# KNOBS.net
KiCad netlist of a schematic drawn in Altium Designer
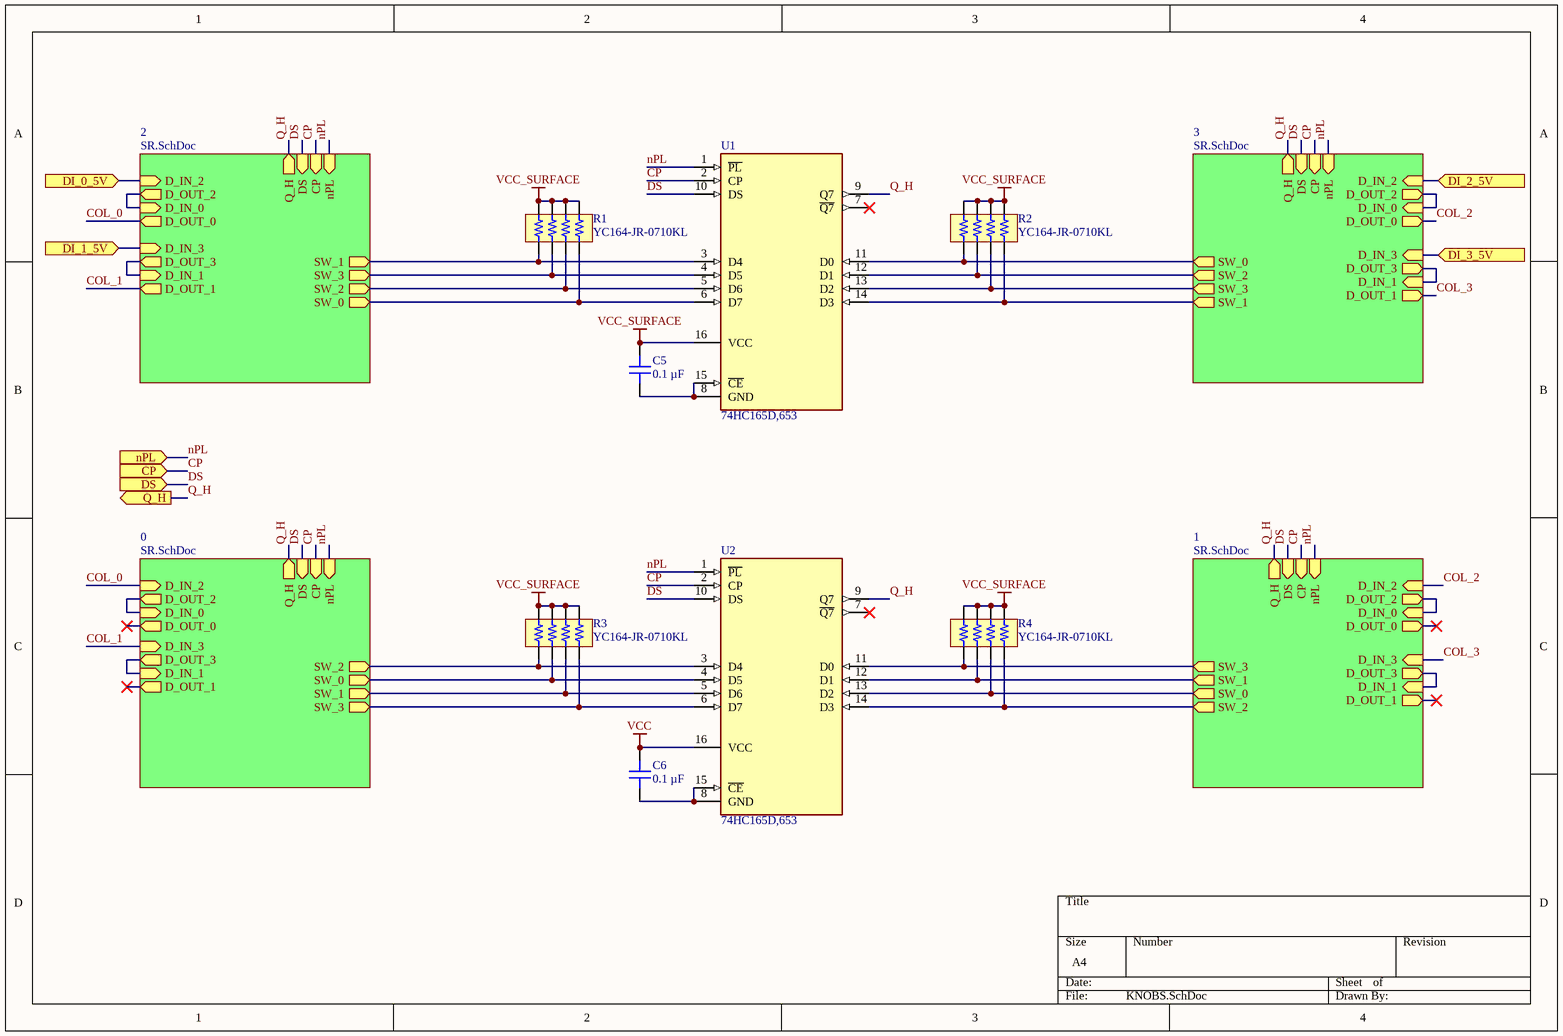
[diagram p0: KNOBS.SchDoc]

(export (version "E")
  (design (tool "Eeschema 10.0.6"))
  (components
    (comp (ref "C5")
      (value "0.1 µF")
      (footprint "CAP 0603_1608")
      (description "CAP CER 0.1UF 16V X7R 0603")
      (fields (field (name "PART NUMBER") "CC0603KPX7R7BB104") (field (name "MANUFACTURER") "Yageo"))
      (libsource (lib "Celestial Altium Library - altium_library") (part "Capacitor"))
    )
    (comp (ref "C6")
      (value "0.1 µF")
      (footprint "CAP 0603_1608")
      (description "CAP CER 0.1UF 16V X7R 0603")
      (fields (field (name "PART NUMBER") "CC0603KPX7R7BB104") (field (name "MANUFACTURER") "Yageo"))
      (libsource (lib "Celestial Altium Library - altium_library") (part "Capacitor"))
    )
    (comp (ref "R1")
      (value "YC164-JR-0710KL")
      (footprint "RESNET 1206-8 CONVEX")
      (description "RES ARRAY 4 RES 10K OHM 1206")
      (fields (field (name "MANUFACTURER") "Yageo") (field (name "TOLERANCE") "±5%"))
      (libsource (lib "Celestial Altium Library - altium_library") (part "Resistor Array (4 circuit)"))
    )
    (comp (ref "R2")
      (value "YC164-JR-0710KL")
      (footprint "RESNET 1206-8 CONVEX")
      (description "RES ARRAY 4 RES 10K OHM 1206")
      (fields (field (name "MANUFACTURER") "Yageo") (field (name "TOLERANCE") "±5%"))
      (libsource (lib "Celestial Altium Library - altium_library") (part "Resistor Array (4 circuit)"))
    )
    (comp (ref "R3")
      (value "YC164-JR-0710KL")
      (footprint "RESNET 1206-8 CONVEX")
      (description "RES ARRAY 4 RES 10K OHM 1206")
      (fields (field (name "MANUFACTURER") "Yageo") (field (name "TOLERANCE") "±5%"))
      (libsource (lib "Celestial Altium Library - altium_library") (part "Resistor Array (4 circuit)"))
    )
    (comp (ref "R4")
      (value "YC164-JR-0710KL")
      (footprint "RESNET 1206-8 CONVEX")
      (description "RES ARRAY 4 RES 10K OHM 1206")
      (fields (field (name "MANUFACTURER") "Yageo") (field (name "TOLERANCE") "±5%"))
      (libsource (lib "Celestial Altium Library - altium_library") (part "Resistor Array (4 circuit)"))
    )
    (comp (ref "U1")
      (value "74HC165D,653")
      (footprint "FP-SOT109-1-MFG")
      (description "IC SHIFT REGST 8BIT PI-SO 16SOIC")
      (fields
        (field (name "MANUFACTURER") "Nexperia")
        (field (name "OCTOPART") "https://octopart.com/74hc165d%2C653-nexperia-78737091")
      )
      (libsource (lib "Altium Content Vault") (part "62206be407dde36a55674a9f8997e2d"))
    )
    (comp (ref "U2")
      (value "74HC165D,653")
      (footprint "FP-SOT109-1-MFG")
      (description "IC SHIFT REGST 8BIT PI-SO 16SOIC")
      (fields
        (field (name "MANUFACTURER") "Nexperia")
        (field (name "OCTOPART") "https://octopart.com/74hc165d%2C653-nexperia-78737091")
      )
      (libsource (lib "Altium Content Vault") (part "62206be407dde36a55674a9f8997e2d"))
    )
  )
  (nets
    (net (code "5") (name "/CP") (class "Default")
      (node (ref "U1") (pin "2") (pinfunction "CP_2") (pintype "input"))
      (node (ref "U2") (pin "2") (pinfunction "CP_2") (pintype "input"))
    )
    (net (code "10") (name "/DS") (class "Default")
      (node (ref "U1") (pin "10") (pinfunction "DS_10") (pintype "input"))
      (node (ref "U2") (pin "10") (pinfunction "DS_10") (pintype "input"))
    )
    (net (code "23") (name "/Q_H") (class "Default")
      (node (ref "U1") (pin "9") (pinfunction "Q7_9") (pintype "output"))
      (node (ref "U2") (pin "9") (pinfunction "Q7_9") (pintype "output"))
    )
    (net (code "24") (name "/SW_0") (class "Default")
      (node (ref "R4") (pin "3") (pinfunction "3_3") (pintype "passive"))
      (node (ref "U2") (pin "13") (pinfunction "D2_13") (pintype "input"))
    )
    (net (code "25") (name "/SW_0_1") (class "Default")
      (node (ref "R1") (pin "4") (pinfunction "4_4") (pintype "passive"))
      (node (ref "U1") (pin "6") (pinfunction "D7_6") (pintype "input"))
    )
    (net (code "26") (name "/SW_0_2") (class "Default")
      (node (ref "R2") (pin "1") (pinfunction "1_1") (pintype "passive"))
      (node (ref "U1") (pin "11") (pinfunction "D0_11") (pintype "input"))
    )
    (net (code "27") (name "/SW_0_3") (class "Default")
      (node (ref "R3") (pin "2") (pinfunction "2_2") (pintype "passive"))
      (node (ref "U2") (pin "4") (pinfunction "D5_4") (pintype "input"))
    )
    (net (code "28") (name "/SW_1") (class "Default")
      (node (ref "R4") (pin "2") (pinfunction "2_2") (pintype "passive"))
      (node (ref "U2") (pin "12") (pinfunction "D1_12") (pintype "input"))
    )
    (net (code "29") (name "/SW_1_1") (class "Default")
      (node (ref "R2") (pin "4") (pinfunction "4_4") (pintype "passive"))
      (node (ref "U1") (pin "14") (pinfunction "D3_14") (pintype "input"))
    )
    (net (code "30") (name "/SW_1_2") (class "Default")
      (node (ref "R1") (pin "1") (pinfunction "1_1") (pintype "passive"))
      (node (ref "U1") (pin "3") (pinfunction "D4_3") (pintype "input"))
    )
    (net (code "31") (name "/SW_1_3") (class "Default")
      (node (ref "R3") (pin "3") (pinfunction "3_3") (pintype "passive"))
      (node (ref "U2") (pin "5") (pinfunction "D6_5") (pintype "input"))
    )
    (net (code "32") (name "/SW_2") (class "Default")
      (node (ref "R4") (pin "4") (pinfunction "4_4") (pintype "passive"))
      (node (ref "U2") (pin "14") (pinfunction "D3_14") (pintype "input"))
    )
    (net (code "33") (name "/SW_2_1") (class "Default")
      (node (ref "R1") (pin "3") (pinfunction "3_3") (pintype "passive"))
      (node (ref "U1") (pin "5") (pinfunction "D6_5") (pintype "input"))
    )
    (net (code "34") (name "/SW_2_2") (class "Default")
      (node (ref "R2") (pin "2") (pinfunction "2_2") (pintype "passive"))
      (node (ref "U1") (pin "12") (pinfunction "D1_12") (pintype "input"))
    )
    (net (code "35") (name "/SW_2_3") (class "Default")
      (node (ref "R3") (pin "1") (pinfunction "1_1") (pintype "passive"))
      (node (ref "U2") (pin "3") (pinfunction "D4_3") (pintype "input"))
    )
    (net (code "36") (name "/SW_3") (class "Default")
      (node (ref "R4") (pin "1") (pinfunction "1_1") (pintype "passive"))
      (node (ref "U2") (pin "11") (pinfunction "D0_11") (pintype "input"))
    )
    (net (code "37") (name "/SW_3_1") (class "Default")
      (node (ref "R2") (pin "3") (pinfunction "3_3") (pintype "passive"))
      (node (ref "U1") (pin "13") (pinfunction "D2_13") (pintype "input"))
    )
    (net (code "38") (name "/SW_3_2") (class "Default")
      (node (ref "R1") (pin "2") (pinfunction "2_2") (pintype "passive"))
      (node (ref "U1") (pin "4") (pinfunction "D5_4") (pintype "input"))
    )
    (net (code "39") (name "/SW_3_3") (class "Default")
      (node (ref "R3") (pin "4") (pinfunction "4_4") (pintype "passive"))
      (node (ref "U2") (pin "6") (pinfunction "D7_6") (pintype "input"))
    )
    (net (code "40") (name "/nPL") (class "Default")
      (node (ref "U1") (pin "1") (pinfunction "~{PL}_1") (pintype "input"))
      (node (ref "U2") (pin "1") (pinfunction "~{PL}_1") (pintype "input"))
    )
    (net (code "41") (name "Net-(U1-GND)") (class "Default")
      (node (ref "C5") (pin "1") (pinfunction "1_1") (pintype "passive"))
      (node (ref "U1") (pin "15") (pinfunction "~{CE}_15") (pintype "input"))
      (node (ref "U1") (pin "8") (pinfunction "GND_8") (pintype "power_in"))
    )
    (net (code "42") (name "Net-(U2-GND)") (class "Default")
      (node (ref "C6") (pin "1") (pinfunction "1_1") (pintype "passive"))
      (node (ref "U2") (pin "15") (pinfunction "~{CE}_15") (pintype "input"))
      (node (ref "U2") (pin "8") (pinfunction "GND_8") (pintype "power_in"))
    )
    (net (code "43") (name "VCC") (class "Default")
      (node (ref "C6") (pin "2") (pinfunction "2_2") (pintype "passive"))
      (node (ref "U2") (pin "16") (pinfunction "VCC_16") (pintype "power_in"))
    )
    (net (code "44") (name "VCC_SURFACE") (class "Default")
      (node (ref "C5") (pin "2") (pinfunction "2_2") (pintype "passive"))
      (node (ref "R1") (pin "5") (pinfunction "5_5") (pintype "passive"))
      (node (ref "R1") (pin "6") (pinfunction "6_6") (pintype "passive"))
      (node (ref "R1") (pin "7") (pinfunction "7_7") (pintype "passive"))
      (node (ref "R1") (pin "8") (pinfunction "8_8") (pintype "passive"))
      (node (ref "R2") (pin "5") (pinfunction "5_5") (pintype "passive"))
      (node (ref "R2") (pin "6") (pinfunction "6_6") (pintype "passive"))
      (node (ref "R2") (pin "7") (pinfunction "7_7") (pintype "passive"))
      (node (ref "R2") (pin "8") (pinfunction "8_8") (pintype "passive"))
      (node (ref "R3") (pin "5") (pinfunction "5_5") (pintype "passive"))
      (node (ref "R3") (pin "6") (pinfunction "6_6") (pintype "passive"))
      (node (ref "R3") (pin "7") (pinfunction "7_7") (pintype "passive"))
      (node (ref "R3") (pin "8") (pinfunction "8_8") (pintype "passive"))
      (node (ref "R4") (pin "5") (pinfunction "5_5") (pintype "passive"))
      (node (ref "R4") (pin "6") (pinfunction "6_6") (pintype "passive"))
      (node (ref "R4") (pin "7") (pinfunction "7_7") (pintype "passive"))
      (node (ref "R4") (pin "8") (pinfunction "8_8") (pintype "passive"))
      (node (ref "U1") (pin "16") (pinfunction "VCC_16") (pintype "power_in"))
    )
    (net (code "45") (name "unconnected-(U1-~{Q7}-Pad7)") (class "Default")
      (node (ref "U1") (pin "7") (pinfunction "~{Q7}_7") (pintype "output+no_connect"))
    )
    (net (code "46") (name "unconnected-(U2-~{Q7}-Pad7)") (class "Default")
      (node (ref "U2") (pin "7") (pinfunction "~{Q7}_7") (pintype "output+no_connect"))
    )
  )
)
